# PA_stage_2.net
KiCad netlist of a schematic drawn in Altium Designer
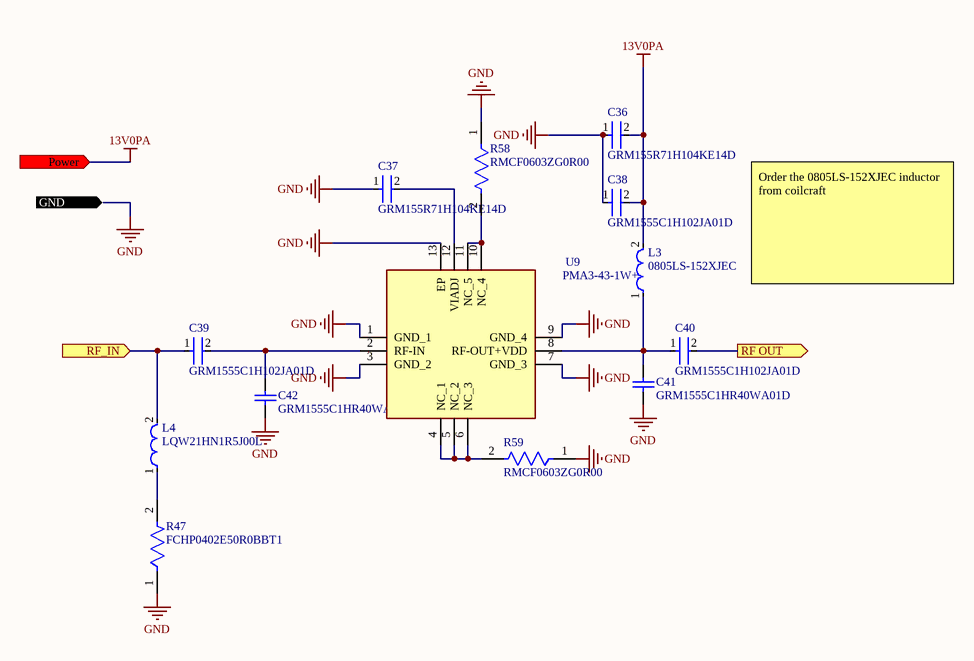
[diagram p0: PA stage 2.SchDoc]

(export (version "E")
  (design (tool "Eeschema 10.0.6"))
  (components
    (comp (ref "C36")
      (value "GRM155R71H104KE14D")
      (footprint "FP-GRM155-0_05-IPC_B")
      (description "Chip Multilayer Ceramic Capacitors for General Purpose, 0402, 0.10uF, X7R, 15%, 10%, 50V")
      (fields (field (name "VOLTAGE") "50V") (field (name "TOLERANCE") "10%"))
      (libsource (lib "Altium Content Vault") (part "02cd4be3c70576c341d710602a673aa"))
    )
    (comp (ref "C37")
      (value "GRM155R71H104KE14D")
      (footprint "FP-GRM155-0_05-IPC_B")
      (description "Chip Multilayer Ceramic Capacitors for General Purpose, 0402, 0.10uF, X7R, 15%, 10%, 50V")
      (fields (field (name "VOLTAGE") "50V") (field (name "TOLERANCE") "10%"))
      (libsource (lib "Altium Content Vault") (part "02cd4be3c70576c341d710602a673aa"))
    )
    (comp (ref "C38")
      (value "GRM1555C1H102JA01D")
      (footprint "FP-GRM155-0_05-IPC_B")
      (description "Chip Multilayer Ceramic Capacitors for General Purpose, 0402, 1000pF, C0G, 30ppm/°C, 5%, 50V")
      (fields (field (name "TOLERANCE") "5%") (field (name "VOLTAGE") "50V"))
      (libsource (lib "Altium Content Vault") (part "02cd4be3c70576c341d710602a673aa"))
    )
    (comp (ref "C39")
      (value "GRM1555C1H102JA01D")
      (footprint "FP-GRM155-0_05-IPC_B")
      (description "Chip Multilayer Ceramic Capacitors for General Purpose, 0402, 1000pF, C0G, 30ppm/°C, 5%, 50V")
      (fields (field (name "TOLERANCE") "5%") (field (name "VOLTAGE") "50V"))
      (libsource (lib "Altium Content Vault") (part "02cd4be3c70576c341d710602a673aa"))
    )
    (comp (ref "C40")
      (value "GRM1555C1H102JA01D")
      (footprint "FP-GRM155-0_05-IPC_B")
      (description "Chip Multilayer Ceramic Capacitors for General Purpose, 0402, 1000pF, C0G, 30ppm/°C, 5%, 50V")
      (fields (field (name "TOLERANCE") "5%") (field (name "VOLTAGE") "50V"))
      (libsource (lib "Altium Content Vault") (part "02cd4be3c70576c341d710602a673aa"))
    )
    (comp (ref "C41")
      (value "GRM1555C1HR40WA01D")
      (footprint "CAPC1005X55X25LL05T10")
      (fields (field (name "MANUFACTURER") "Murata"))
      (libsource (lib "Altium Content Vault") (part "CAP"))
    )
    (comp (ref "C42")
      (value "GRM1555C1HR40WA01D")
      (footprint "CAPC1005X55X25LL05T10")
      (fields (field (name "MANUFACTURER") "Murata"))
      (libsource (lib "Altium Content Vault") (part "CAP"))
    )
    (comp (ref "L3")
      (value "0805LS-152XJEC")
      (footprint "FP-LQW21HN_00-MFG")
      (description "0805LS-152XJEC Coilcraft")
      (fields (field (name "TOLERANCE") "5%"))
      (libsource (lib "Altium Content Vault") (part "725321dda6339637d4d059423bc1c3c"))
    )
    (comp (ref "L4")
      (value "LQW21HN1R5J00L")
      (footprint "FP-LQW21HN_00-MFG")
      (description "Wire Wound Ferrite type RF Inuctor 1.5uH ±5% 85mA 5.33Ω 0805 (2012)")
      (fields (field (name "TOLERANCE") "5%"))
      (libsource (lib "Altium Content Vault") (part "725321dda6339637d4d059423bc1c3c"))
    )
    (comp (ref "R47")
      (value "FCHP0402E50R0BBT1")
      (footprint "FP-FC0402-MFG")
      (fields (field (name "TOLERANCE") "0.1%"))
      (libsource (lib "Altium Content Vault") (part "1029c3af85768c4190bb7ad29bc67b5"))
    )
    (comp (ref "R58")
      (value "RMCF0603ZG0R00")
      (footprint "FP-RMCF0603-IPC_B")
      (description "0Ω ±0 0.1W 0603 Thick Film Chip Resistor AEC-Q200 compliant")
      (libsource (lib "Altium Content Vault") (part "1029c3af85768c4190bb7ad29bc67b5"))
    )
    (comp (ref "R59")
      (value "RMCF0603ZG0R00")
      (footprint "FP-RMCF0603-IPC_B")
      (description "0Ω ±0 0.1W 0603 Thick Film Chip Resistor AEC-Q200 compliant")
      (libsource (lib "Altium Content Vault") (part "1029c3af85768c4190bb7ad29bc67b5"))
    )
    (comp (ref "U9")
      (value "PMA3-43-1W+")
      (footprint "QFN51P300X300X89-13N")
      (description "Integrated Circuit")
      (libsource (lib "SamacSys") (part "PMA3-43-1W+"))
    )
  )
  (nets
    (net (code "1") (name "/RF OUT") (class "Default")
      (node (ref "C40") (pin "2") (pinfunction "2_2") (pintype "passive"))
    )
    (net (code "2") (name "/RF_IN") (class "Default")
      (node (ref "C39") (pin "1") (pinfunction "1_1") (pintype "passive"))
      (node (ref "L4") (pin "2") (pinfunction "2_2") (pintype "passive"))
    )
    (net (code "3") (name "13V0PA") (class "Default")
      (node (ref "C36") (pin "2") (pinfunction "2_2") (pintype "passive"))
      (node (ref "C38") (pin "2") (pinfunction "2_2") (pintype "passive"))
      (node (ref "L3") (pin "2") (pinfunction "2_2") (pintype "passive"))
    )
    (net (code "4") (name "GND") (class "Default")
      (node (ref "C36") (pin "1") (pinfunction "1_1") (pintype "passive"))
      (node (ref "C37") (pin "1") (pinfunction "1_1") (pintype "passive"))
      (node (ref "C38") (pin "1") (pinfunction "1_1") (pintype "passive"))
      (node (ref "C41") (pin "1") (pinfunction "1_1") (pintype "passive"))
      (node (ref "C42") (pin "1") (pinfunction "1_1") (pintype "passive"))
      (node (ref "R47") (pin "1") (pinfunction "1_1") (pintype "passive"))
      (node (ref "R58") (pin "1") (pinfunction "1_1") (pintype "passive"))
      (node (ref "R59") (pin "1") (pinfunction "1_1") (pintype "passive"))
      (node (ref "U9") (pin "1") (pinfunction "GND_1_1") (pintype "passive"))
      (node (ref "U9") (pin "13") (pinfunction "EP_13") (pintype "passive"))
      (node (ref "U9") (pin "3") (pinfunction "GND_2_3") (pintype "passive"))
      (node (ref "U9") (pin "7") (pinfunction "GND_3_7") (pintype "passive"))
      (node (ref "U9") (pin "9") (pinfunction "GND_4_9") (pintype "passive"))
    )
    (net (code "5") (name "Net-(L4-Pad1)") (class "Default")
      (node (ref "L4") (pin "1") (pinfunction "1_1") (pintype "passive"))
      (node (ref "R47") (pin "2") (pinfunction "2_2") (pintype "passive"))
    )
    (net (code "6") (name "Net-(U9-NC_1)") (class "Default")
      (node (ref "R59") (pin "2") (pinfunction "2_2") (pintype "passive"))
      (node (ref "U9") (pin "4") (pinfunction "NC_1_4") (pintype "passive"))
      (node (ref "U9") (pin "5") (pinfunction "NC_2_5") (pintype "passive"))
      (node (ref "U9") (pin "6") (pinfunction "NC_3_6") (pintype "passive"))
    )
    (net (code "7") (name "Net-(U9-NC_4)") (class "Default")
      (node (ref "R58") (pin "2") (pinfunction "2_2") (pintype "passive"))
      (node (ref "U9") (pin "10") (pinfunction "NC_4_10") (pintype "passive"))
      (node (ref "U9") (pin "11") (pinfunction "NC_5_11") (pintype "passive"))
    )
    (net (code "8") (name "Net-(U9-RF-IN)") (class "Default")
      (node (ref "C39") (pin "2") (pinfunction "2_2") (pintype "passive"))
      (node (ref "C42") (pin "2") (pinfunction "2_2") (pintype "passive"))
      (node (ref "U9") (pin "2") (pinfunction "RF-IN_2") (pintype "passive"))
    )
    (net (code "9") (name "Net-(U9-RF-OUT+VDD)") (class "Default")
      (node (ref "C40") (pin "1") (pinfunction "1_1") (pintype "passive"))
      (node (ref "C41") (pin "2") (pinfunction "2_2") (pintype "passive"))
      (node (ref "L3") (pin "1") (pinfunction "1_1") (pintype "passive"))
      (node (ref "U9") (pin "8") (pinfunction "RF-OUT+VDD_8") (pintype "passive"))
    )
    (net (code "10") (name "Net-(U9-VIADJ)") (class "Default")
      (node (ref "C37") (pin "2") (pinfunction "2_2") (pintype "passive"))
      (node (ref "U9") (pin "12") (pinfunction "VIADJ_12") (pintype "passive"))
    )
  )
)
